# entrenador.net
KiCad netlist of a schematic drawn in EAGLE
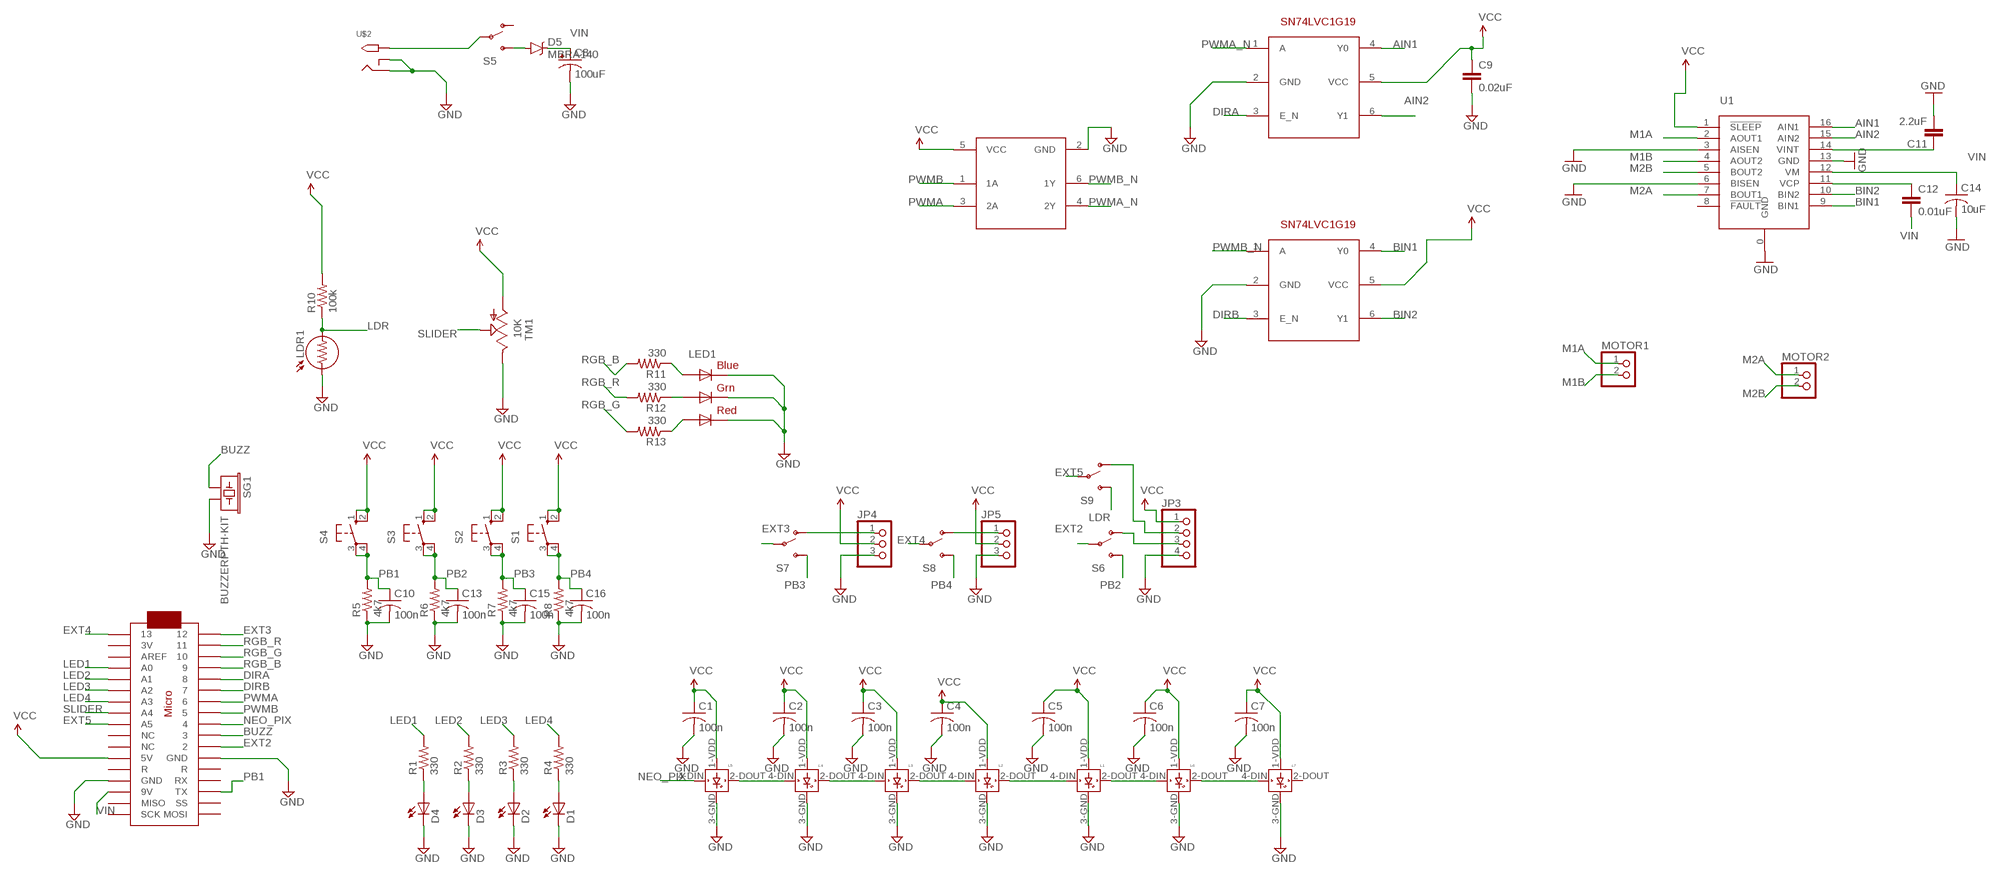
[diagram p0: schematic, sheet 1]

(export (version "E")
  (design (tool "Eeschema 10.0.6"))
  (components
    (comp (ref "C1")
      (value "100n")
      (footprint "eagle-import:C0805")
      (libsource (lib "eagle-import") (part "C-USC0805"))
    )
    (comp (ref "C2")
      (value "100n")
      (footprint "eagle-import:C0805")
      (libsource (lib "eagle-import") (part "C-USC0805"))
    )
    (comp (ref "C3")
      (value "100n")
      (footprint "eagle-import:C0805")
      (libsource (lib "eagle-import") (part "C-USC0805"))
    )
    (comp (ref "C4")
      (value "100n")
      (footprint "eagle-import:C0805")
      (libsource (lib "eagle-import") (part "C-USC0805"))
    )
    (comp (ref "C5")
      (value "100n")
      (footprint "eagle-import:C0805")
      (libsource (lib "eagle-import") (part "C-USC0805"))
    )
    (comp (ref "C6")
      (value "100n")
      (footprint "eagle-import:C0805")
      (libsource (lib "eagle-import") (part "C-USC0805"))
    )
    (comp (ref "C7")
      (value "100n")
      (footprint "eagle-import:C0805")
      (libsource (lib "eagle-import") (part "C-USC0805"))
    )
    (comp (ref "C8")
      (value "100uF")
      (footprint "eagle-import:175TMP-0808")
      (libsource (lib "eagle-import") (part "CPOL-US175TMP-0808"))
    )
    (comp (ref "C9")
      (value "0.02uF")
      (footprint "eagle-import:C0805")
      (libsource (lib "eagle-import") (part "C-EUC0805"))
    )
    (comp (ref "C10")
      (value "100n")
      (footprint "eagle-import:C0805")
      (libsource (lib "eagle-import") (part "C-USC0805"))
    )
    (comp (ref "C11")
      (value "2.2uF")
      (footprint "eagle-import:C0805")
      (libsource (lib "eagle-import") (part "C-EUC0805"))
    )
    (comp (ref "C12")
      (value "0.01uF")
      (footprint "eagle-import:C0805")
      (libsource (lib "eagle-import") (part "C-EUC0805"))
    )
    (comp (ref "C13")
      (value "100n")
      (footprint "eagle-import:C0805")
      (libsource (lib "eagle-import") (part "C-USC0805"))
    )
    (comp (ref "C14")
      (value "10uF")
      (footprint "eagle-import:C0805K")
      (libsource (lib "eagle-import") (part "C-USC0805K"))
    )
    (comp (ref "C15")
      (value "100n")
      (footprint "eagle-import:C0805")
      (libsource (lib "eagle-import") (part "C-USC0805"))
    )
    (comp (ref "C16")
      (value "100n")
      (footprint "eagle-import:C0805")
      (libsource (lib "eagle-import") (part "C-USC0805"))
    )
    (comp (ref "D1")
      (value "LED5MM")
      (footprint "eagle-import:LED5MM")
      (libsource (lib "eagle-import") (part "LED5MM"))
    )
    (comp (ref "D2")
      (value "LED5MM")
      (footprint "eagle-import:LED5MM")
      (libsource (lib "eagle-import") (part "LED5MM"))
    )
    (comp (ref "D3")
      (value "LED5MM")
      (footprint "eagle-import:LED5MM")
      (libsource (lib "eagle-import") (part "LED5MM"))
    )
    (comp (ref "D4")
      (value "LED5MM")
      (footprint "eagle-import:LED5MM")
      (libsource (lib "eagle-import") (part "LED5MM"))
    )
    (comp (ref "D5")
      (value "MBRA140")
      (footprint "eagle-import:SMA-DIODE")
      (libsource (lib "eagle-import") (part "MBRA140"))
    )
    (comp (ref "JP3")
      (value "PINHD-1X4/90")
      (footprint "eagle-import:1X04_90")
      (libsource (lib "eagle-import") (part "PINHD-1X4/90"))
    )
    (comp (ref "JP4")
      (value "PINHD-1X3/90")
      (footprint "eagle-import:1X03_90")
      (libsource (lib "eagle-import") (part "PINHD-1X3/90"))
    )
    (comp (ref "JP5")
      (value "PINHD-1X3/90")
      (footprint "eagle-import:1X03_90")
      (libsource (lib "eagle-import") (part "PINHD-1X3/90"))
    )
    (comp (ref "L1")
      (value "WS2812B")
      (footprint "eagle-import:WS2812B")
      (libsource (lib "eagle-import") (part "WS2812B"))
    )
    (comp (ref "L2")
      (value "WS2812B")
      (footprint "eagle-import:WS2812B")
      (libsource (lib "eagle-import") (part "WS2812B"))
    )
    (comp (ref "L3")
      (value "WS2812B")
      (footprint "eagle-import:WS2812B")
      (libsource (lib "eagle-import") (part "WS2812B"))
    )
    (comp (ref "L4")
      (value "WS2812B")
      (footprint "eagle-import:WS2812B")
      (libsource (lib "eagle-import") (part "WS2812B"))
    )
    (comp (ref "L5")
      (value "WS2812B")
      (footprint "eagle-import:WS2812B")
      (libsource (lib "eagle-import") (part "WS2812B"))
    )
    (comp (ref "L6")
      (value "WS2812B")
      (footprint "eagle-import:WS2812B")
      (libsource (lib "eagle-import") (part "WS2812B"))
    )
    (comp (ref "L7")
      (value "WS2812B")
      (footprint "eagle-import:WS2812B")
      (libsource (lib "eagle-import") (part "WS2812B"))
    )
    (comp (ref "LDR1")
      (value "LDR5MM")
      (footprint "eagle-import:LDR338-54C")
      (libsource (lib "eagle-import") (part "LDR5MM"))
    )
    (comp (ref "LED1")
      (value "RGBLED5050")
      (footprint "eagle-import:RGBLED5050")
      (libsource (lib "eagle-import") (part "RGBLED5050"))
    )
    (comp (ref "MOTOR1")
      (value "PINHD-1X2/90")
      (footprint "eagle-import:1X02_90")
      (libsource (lib "eagle-import") (part "PINHD-1X2/90"))
    )
    (comp (ref "MOTOR2")
      (value "PINHD-1X2/90")
      (footprint "eagle-import:1X02_90")
      (libsource (lib "eagle-import") (part "PINHD-1X2/90"))
    )
    (comp (ref "R1")
      (value "330")
      (footprint "eagle-import:M0805")
      (libsource (lib "eagle-import") (part "R-US_M0805"))
    )
    (comp (ref "R2")
      (value "330")
      (footprint "eagle-import:M0805")
      (libsource (lib "eagle-import") (part "R-US_M0805"))
    )
    (comp (ref "R3")
      (value "330")
      (footprint "eagle-import:M0805")
      (libsource (lib "eagle-import") (part "R-US_M0805"))
    )
    (comp (ref "R4")
      (value "330")
      (footprint "eagle-import:M0805")
      (libsource (lib "eagle-import") (part "R-US_M0805"))
    )
    (comp (ref "R5")
      (value "4k7")
      (footprint "eagle-import:M0805")
      (libsource (lib "eagle-import") (part "R-US_M0805"))
    )
    (comp (ref "R6")
      (value "4k7")
      (footprint "eagle-import:M0805")
      (libsource (lib "eagle-import") (part "R-US_M0805"))
    )
    (comp (ref "R7")
      (value "4k7")
      (footprint "eagle-import:M0805")
      (libsource (lib "eagle-import") (part "R-US_M0805"))
    )
    (comp (ref "R8")
      (value "4k7")
      (footprint "eagle-import:M0805")
      (libsource (lib "eagle-import") (part "R-US_M0805"))
    )
    (comp (ref "R10")
      (value "100k")
      (footprint "eagle-import:M0805")
      (libsource (lib "eagle-import") (part "R-US_M0805"))
    )
    (comp (ref "R11")
      (value "330")
      (footprint "eagle-import:M0805")
      (libsource (lib "eagle-import") (part "R-US_M0805"))
    )
    (comp (ref "R12")
      (value "330")
      (footprint "eagle-import:M0805")
      (libsource (lib "eagle-import") (part "R-US_M0805"))
    )
    (comp (ref "R13")
      (value "330")
      (footprint "eagle-import:M0805")
      (libsource (lib "eagle-import") (part "R-US_M0805"))
    )
    (comp (ref "S1")
      (value "40-XX-ROUND")
      (footprint "eagle-import:B3F-40XX-ROUND")
      (libsource (lib "eagle-import") (part "40-XX-ROUND"))
    )
    (comp (ref "S2")
      (value "40-XX-ROUND")
      (footprint "eagle-import:B3F-40XX-ROUND")
      (libsource (lib "eagle-import") (part "40-XX-ROUND"))
    )
    (comp (ref "S3")
      (value "40-XX-ROUND")
      (footprint "eagle-import:B3F-40XX-ROUND")
      (libsource (lib "eagle-import") (part "40-XX-ROUND"))
    )
    (comp (ref "S4")
      (value "40-XX-ROUND")
      (footprint "eagle-import:B3F-40XX-ROUND")
      (libsource (lib "eagle-import") (part "40-XX-ROUND"))
    )
    (comp (ref "S5")
      (value "SWITCH-SPDT-SMD-A")
      (footprint "eagle-import:SWITCH-SPST-SMD-A")
      (libsource (lib "eagle-import") (part "SWITCH-SPDT-SMD-A"))
    )
    (comp (ref "S6")
      (value "SWITCH-SPDTSS-12F44")
      (footprint "eagle-import:SS-12F44G4")
      (libsource (lib "eagle-import") (part "SWITCH-SPDTSS-12F44"))
    )
    (comp (ref "S7")
      (value "SWITCH-SPDTSS-12F44")
      (footprint "eagle-import:SS-12F44G4")
      (libsource (lib "eagle-import") (part "SWITCH-SPDTSS-12F44"))
    )
    (comp (ref "S8")
      (value "SWITCH-SPDTSS-12F44")
      (footprint "eagle-import:SS-12F44G4")
      (libsource (lib "eagle-import") (part "SWITCH-SPDTSS-12F44"))
    )
    (comp (ref "S9")
      (value "SWITCH-SPDTSS-12F44")
      (footprint "eagle-import:SS-12F44G4")
      (libsource (lib "eagle-import") (part "SWITCH-SPDTSS-12F44"))
    )
    (comp (ref "SG1")
      (value "BUZZERPTH-KIT")
      (footprint "eagle-import:BUZZER-12MM-KIT")
      (libsource (lib "eagle-import") (part "BUZZERPTH-KIT"))
    )
    (comp (ref "TM1")
      (value "10K")
      (footprint "eagle-import:SLIDEPOT-60")
      (libsource (lib "eagle-import") (part "TRIMSLIDEPOT-60"))
    )
    (comp (ref "U$1")
      (value "SN74LVC1G19SN74LVC1G19-DBVR")
      (footprint "eagle-import:SOT23-6")
      (libsource (lib "eagle-import") (part "SN74LVC1G19SN74LVC1G19-DBVR"))
    )
    (comp (ref "U$2")
      (value "2.1MMJACKTHM")
      (footprint "eagle-import:PJ-102A")
      (libsource (lib "eagle-import") (part "2.1MMJACKTHM"))
    )
    (comp (ref "U$8")
      (value "ARDUINOMICRO")
      (footprint "eagle-import:ARDUINOMICRO")
      (libsource (lib "eagle-import") (part "ARDUINOMICRO"))
    )
    (comp (ref "U$9")
      (value "SN74LVC1G19SN74LVC1G19-DBVR")
      (footprint "eagle-import:SOT23-6")
      (libsource (lib "eagle-import") (part "SN74LVC1G19SN74LVC1G19-DBVR"))
    )
    (comp (ref "U$10")
      (value "SN74LVC2G04SOT23-6")
      (footprint "eagle-import:SOT23-6")
      (libsource (lib "eagle-import") (part "SN74LVC2G04SOT23-6"))
    )
    (comp (ref "U1")
      (value "DRV8833")
      (footprint "eagle-import:PWP16")
      (libsource (lib "eagle-import") (part "DRV8833"))
    )
  )
  (nets
    (net (code "1") (name "/AIN1") (class "Default")
      (node (ref "U$1") (pin "4") (pinfunction "Y0_4") (pintype "bidirectional"))
      (node (ref "U1") (pin "16") (pinfunction "AIN1_16") (pintype "bidirectional"))
    )
    (net (code "2") (name "/AIN2") (class "Default")
      (node (ref "U$1") (pin "6") (pinfunction "Y1_6") (pintype "bidirectional"))
      (node (ref "U1") (pin "15") (pinfunction "AIN2_15") (pintype "bidirectional"))
    )
    (net (code "3") (name "/BIN1") (class "Default")
      (node (ref "U$9") (pin "4") (pinfunction "Y0_4") (pintype "bidirectional"))
      (node (ref "U1") (pin "9") (pinfunction "BIN1_9") (pintype "bidirectional"))
    )
    (net (code "4") (name "/BIN2") (class "Default")
      (node (ref "U$9") (pin "6") (pinfunction "Y1_6") (pintype "bidirectional"))
      (node (ref "U1") (pin "10") (pinfunction "BIN2_10") (pintype "bidirectional"))
    )
    (net (code "5") (name "/BUZZ") (class "Default")
      (node (ref "SG1") (pin "+") (pinfunction "1_+") (pintype "passive"))
      (node (ref "U$8") (pin "P$10") (pinfunction "3_P$10") (pintype "bidirectional"))
    )
    (net (code "6") (name "/DIRA") (class "Default")
      (node (ref "U$1") (pin "3") (pinfunction "E_N_3") (pintype "bidirectional"))
      (node (ref "U$8") (pin "P$5") (pinfunction "8_P$5") (pintype "bidirectional"))
    )
    (net (code "7") (name "/DIRB") (class "Default")
      (node (ref "U$8") (pin "P$6") (pinfunction "7_P$6") (pintype "bidirectional"))
      (node (ref "U$9") (pin "3") (pinfunction "E_N_3") (pintype "bidirectional"))
    )
    (net (code "8") (name "/EXT2") (class "Default")
      (node (ref "S6") (pin "2") (pinfunction "P_2") (pintype "passive"))
      (node (ref "U$8") (pin "P$11") (pinfunction "2_P$11") (pintype "bidirectional"))
    )
    (net (code "9") (name "/EXT3") (class "Default")
      (node (ref "S7") (pin "2") (pinfunction "P_2") (pintype "passive"))
      (node (ref "U$8") (pin "P$1") (pinfunction "12_P$1") (pintype "bidirectional"))
    )
    (net (code "10") (name "/EXT4") (class "Default")
      (node (ref "S8") (pin "2") (pinfunction "P_2") (pintype "passive"))
      (node (ref "U$8") (pin "P$34") (pinfunction "13_P$34") (pintype "bidirectional"))
    )
    (net (code "11") (name "/EXT5") (class "Default")
      (node (ref "S9") (pin "2") (pinfunction "P_2") (pintype "passive"))
      (node (ref "U$8") (pin "P$26") (pinfunction "A5_P$26") (pintype "bidirectional"))
    )
    (net (code "12") (name "/LDR") (class "Default")
      (node (ref "LDR1") (pin "2") (pinfunction "2_2") (pintype "passive"))
      (node (ref "R10") (pin "1") (pinfunction "1_1") (pintype "passive"))
      (node (ref "S9") (pin "3") (pinfunction "S_3") (pintype "passive"))
    )
    (net (code "13") (name "/LED1") (class "Default")
      (node (ref "R1") (pin "2") (pinfunction "2_2") (pintype "passive"))
      (node (ref "U$8") (pin "P$31") (pinfunction "A0_P$31") (pintype "bidirectional"))
    )
    (net (code "14") (name "/LED2") (class "Default")
      (node (ref "R2") (pin "2") (pinfunction "2_2") (pintype "passive"))
      (node (ref "U$8") (pin "P$30") (pinfunction "A1_P$30") (pintype "bidirectional"))
    )
    (net (code "15") (name "/LED3") (class "Default")
      (node (ref "R3") (pin "2") (pinfunction "2_2") (pintype "passive"))
      (node (ref "U$8") (pin "P$29") (pinfunction "A2_P$29") (pintype "bidirectional"))
    )
    (net (code "16") (name "/LED4") (class "Default")
      (node (ref "R4") (pin "2") (pinfunction "2_2") (pintype "passive"))
      (node (ref "U$8") (pin "P$28") (pinfunction "A3_P$28") (pintype "bidirectional"))
    )
    (net (code "17") (name "/M1A") (class "Default")
      (node (ref "MOTOR1") (pin "1") (pinfunction "1_1") (pintype "passive"))
      (node (ref "U1") (pin "2") (pinfunction "AOUT1_2") (pintype "bidirectional"))
    )
    (net (code "18") (name "/M1B") (class "Default")
      (node (ref "MOTOR1") (pin "2") (pinfunction "2_2") (pintype "passive"))
      (node (ref "U1") (pin "4") (pinfunction "AOUT2_4") (pintype "bidirectional"))
    )
    (net (code "19") (name "/M2A") (class "Default")
      (node (ref "MOTOR2") (pin "1") (pinfunction "1_1") (pintype "passive"))
      (node (ref "U1") (pin "7") (pinfunction "BOUT1_7") (pintype "bidirectional"))
    )
    (net (code "20") (name "/M2B") (class "Default")
      (node (ref "MOTOR2") (pin "2") (pinfunction "2_2") (pintype "passive"))
      (node (ref "U1") (pin "5") (pinfunction "BOUT2_5") (pintype "bidirectional"))
    )
    (net (code "21") (name "/NEO_PIX") (class "Default")
      (node (ref "L5") (pin "4-DIN") (pinfunction "DIN_4-DIN") (pintype "input"))
      (node (ref "U$8") (pin "P$9") (pinfunction "4_P$9") (pintype "bidirectional"))
    )
    (net (code "22") (name "/PB1") (class "Default")
      (node (ref "C10") (pin "1") (pinfunction "1_1") (pintype "passive"))
      (node (ref "R5") (pin "2") (pinfunction "2_2") (pintype "passive"))
      (node (ref "S4") (pin "3") (pinfunction "P_3") (pintype "passive"))
      (node (ref "S4") (pin "4") (pinfunction "P1_4") (pintype "passive"))
      (node (ref "U$8") (pin "P$15") (pinfunction "TX_P$15") (pintype "bidirectional"))
    )
    (net (code "23") (name "/PB2") (class "Default")
      (node (ref "C13") (pin "1") (pinfunction "1_1") (pintype "passive"))
      (node (ref "R6") (pin "2") (pinfunction "2_2") (pintype "passive"))
      (node (ref "S3") (pin "3") (pinfunction "P_3") (pintype "passive"))
      (node (ref "S3") (pin "4") (pinfunction "P1_4") (pintype "passive"))
      (node (ref "S6") (pin "3") (pinfunction "S_3") (pintype "passive"))
    )
    (net (code "24") (name "/PB3") (class "Default")
      (node (ref "C15") (pin "1") (pinfunction "1_1") (pintype "passive"))
      (node (ref "R7") (pin "2") (pinfunction "2_2") (pintype "passive"))
      (node (ref "S2") (pin "3") (pinfunction "P_3") (pintype "passive"))
      (node (ref "S2") (pin "4") (pinfunction "P1_4") (pintype "passive"))
      (node (ref "S7") (pin "3") (pinfunction "S_3") (pintype "passive"))
    )
    (net (code "25") (name "/PB4") (class "Default")
      (node (ref "C16") (pin "1") (pinfunction "1_1") (pintype "passive"))
      (node (ref "R8") (pin "2") (pinfunction "2_2") (pintype "passive"))
      (node (ref "S1") (pin "3") (pinfunction "P_3") (pintype "passive"))
      (node (ref "S1") (pin "4") (pinfunction "P1_4") (pintype "passive"))
      (node (ref "S8") (pin "3") (pinfunction "S_3") (pintype "passive"))
    )
    (net (code "26") (name "/PWMA") (class "Default")
      (node (ref "U$10") (pin "3") (pinfunction "2A_3") (pintype "bidirectional"))
      (node (ref "U$8") (pin "P$7") (pinfunction "6_P$7") (pintype "bidirectional"))
    )
    (net (code "27") (name "/PWMA_N") (class "Default")
      (node (ref "U$1") (pin "1") (pinfunction "A_1") (pintype "bidirectional"))
      (node (ref "U$10") (pin "4") (pinfunction "2Y_4") (pintype "bidirectional"))
    )
    (net (code "28") (name "/PWMB") (class "Default")
      (node (ref "U$10") (pin "1") (pinfunction "1A_1") (pintype "bidirectional"))
      (node (ref "U$8") (pin "P$8") (pinfunction "5_P$8") (pintype "bidirectional"))
    )
    (net (code "29") (name "/PWMB_N") (class "Default")
      (node (ref "U$10") (pin "6") (pinfunction "1Y_6") (pintype "bidirectional"))
      (node (ref "U$9") (pin "1") (pinfunction "A_1") (pintype "bidirectional"))
    )
    (net (code "30") (name "/RGB_B") (class "Default")
      (node (ref "R11") (pin "2") (pinfunction "2_2") (pintype "passive"))
      (node (ref "U$8") (pin "P$4") (pinfunction "9_P$4") (pintype "bidirectional"))
    )
    (net (code "31") (name "/RGB_G") (class "Default")
      (node (ref "R13") (pin "2") (pinfunction "2_2") (pintype "passive"))
      (node (ref "U$8") (pin "P$3") (pinfunction "10_P$3") (pintype "bidirectional"))
    )
    (net (code "32") (name "/RGB_R") (class "Default")
      (node (ref "R12") (pin "2") (pinfunction "2_2") (pintype "passive"))
      (node (ref "U$8") (pin "P$2") (pinfunction "11_P$2") (pintype "bidirectional"))
    )
    (net (code "33") (name "/SLIDER") (class "Default")
      (node (ref "TM1") (pin "B") (pinfunction "S_B") (pintype "passive"))
      (node (ref "U$8") (pin "P$27") (pinfunction "A4_P$27") (pintype "bidirectional"))
    )
    (net (code "34") (name "/VIN") (class "Default")
      (node (ref "C12") (pin "2") (pinfunction "2_2") (pintype "passive"))
      (node (ref "C14") (pin "1") (pinfunction "1_1") (pintype "passive"))
      (node (ref "C8") (pin "+") (pinfunction "+_+") (pintype "passive"))
      (node (ref "D5") (pin "C") (pinfunction "C_C") (pintype "passive"))
      (node (ref "U$8") (pin "P$20") (pinfunction "9V_P$20") (pintype "bidirectional"))
      (node (ref "U1") (pin "12") (pinfunction "VM_12") (pintype "bidirectional"))
    )
    (net (code "35") (name "GND") (class "Default")
      (node (ref "C1") (pin "2") (pinfunction "2_2") (pintype "passive"))
      (node (ref "C10") (pin "2") (pinfunction "2_2") (pintype "passive"))
      (node (ref "C11") (pin "2") (pinfunction "2_2") (pintype "passive"))
      (node (ref "C13") (pin "2") (pinfunction "2_2") (pintype "passive"))
      (node (ref "C14") (pin "2") (pinfunction "2_2") (pintype "passive"))
      (node (ref "C15") (pin "2") (pinfunction "2_2") (pintype "passive"))
      (node (ref "C16") (pin "2") (pinfunction "2_2") (pintype "passive"))
      (node (ref "C2") (pin "2") (pinfunction "2_2") (pintype "passive"))
      (node (ref "C3") (pin "2") (pinfunction "2_2") (pintype "passive"))
      (node (ref "C4") (pin "2") (pinfunction "2_2") (pintype "passive"))
      (node (ref "C5") (pin "2") (pinfunction "2_2") (pintype "passive"))
      (node (ref "C6") (pin "2") (pinfunction "2_2") (pintype "passive"))
      (node (ref "C7") (pin "2") (pinfunction "2_2") (pintype "passive"))
      (node (ref "C8") (pin "-") (pinfunction "-_-") (pintype "passive"))
      (node (ref "C9") (pin "2") (pinfunction "2_2") (pintype "passive"))
      (node (ref "D1") (pin "K") (pinfunction "C_K") (pintype "passive"))
      (node (ref "D2") (pin "K") (pinfunction "C_K") (pintype "passive"))
      (node (ref "D3") (pin "K") (pinfunction "C_K") (pintype "passive"))
      (node (ref "D4") (pin "K") (pinfunction "C_K") (pintype "passive"))
      (node (ref "JP3") (pin "4") (pinfunction "4_4") (pintype "passive"))
      (node (ref "JP4") (pin "3") (pinfunction "3_3") (pintype "passive"))
      (node (ref "JP5") (pin "3") (pinfunction "3_3") (pintype "passive"))
      (node (ref "L1") (pin "3-GND") (pinfunction "GND_3-GND") (pintype "bidirectional"))
      (node (ref "L2") (pin "3-GND") (pinfunction "GND_3-GND") (pintype "bidirectional"))
      (node (ref "L3") (pin "3-GND") (pinfunction "GND_3-GND") (pintype "bidirectional"))
      (node (ref "L4") (pin "3-GND") (pinfunction "GND_3-GND") (pintype "bidirectional"))
      (node (ref "L5") (pin "3-GND") (pinfunction "GND_3-GND") (pintype "bidirectional"))
      (node (ref "L6") (pin "3-GND") (pinfunction "GND_3-GND") (pintype "bidirectional"))
      (node (ref "L7") (pin "3-GND") (pinfunction "GND_3-GND") (pintype "bidirectional"))
      (node (ref "LDR1") (pin "1") (pinfunction "1_1") (pintype "passive"))
      (node (ref "LED1") (pin "4") (pinfunction "BLUE_C_4") (pintype "bidirectional"))
      (node (ref "LED1") (pin "5") (pinfunction "RED_C_5") (pintype "bidirectional"))
      (node (ref "LED1") (pin "6") (pinfunction "GREEN_C_6") (pintype "bidirectional"))
      (node (ref "R5") (pin "1") (pinfunction "1_1") (pintype "passive"))
      (node (ref "R6") (pin "1") (pinfunction "1_1") (pintype "passive"))
      (node (ref "R7") (pin "1") (pinfunction "1_1") (pintype "passive"))
      (node (ref "R8") (pin "1") (pinfunction "1_1") (pintype "passive"))
      (node (ref "SG1") (pin "-") (pinfunction "2_-") (pintype "passive"))
      (node (ref "TM1") (pin "C") (pinfunction "E_C") (pintype "passive"))
      (node (ref "U$1") (pin "2") (pinfunction "GND_2") (pintype "bidirectional"))
      (node (ref "U$10") (pin "2") (pinfunction "GND_2") (pintype "bidirectional"))
      (node (ref "U$2") (pin "RING") (pinfunction "RING_RING") (pintype "bidirectional"))
      (node (ref "U$2") (pin "RING_SW") (pinfunction "RING_SW_RING_SW") (pintype "bidirectional"))
      (node (ref "U$8") (pin "P$12") (pinfunction "GND_P$12") (pintype "bidirectional"))
      (node (ref "U$8") (pin "P$21") (pinfunction "GND_P$21") (pintype "bidirectional"))
      (node (ref "U$9") (pin "2") (pinfunction "GND_2") (pintype "bidirectional"))
      (node (ref "U1") (pin "0") (pinfunction "GND_0") (pintype "bidirectional"))
      (node (ref "U1") (pin "13") (pinfunction "GND_13") (pintype "bidirectional"))
      (node (ref "U1") (pin "3") (pinfunction "AISEN_3") (pintype "bidirectional"))
      (node (ref "U1") (pin "6") (pinfunction "BISEN_6") (pintype "bidirectional"))
    )
    (net (code "36") (name "Net-(D1-PadA)") (class "Default")
      (node (ref "D1") (pin "A") (pinfunction "A_A") (pintype "passive"))
      (node (ref "R4") (pin "1") (pinfunction "1_1") (pintype "passive"))
    )
    (net (code "37") (name "Net-(D2-PadA)") (class "Default")
      (node (ref "D2") (pin "A") (pinfunction "A_A") (pintype "passive"))
      (node (ref "R3") (pin "1") (pinfunction "1_1") (pintype "passive"))
    )
    (net (code "38") (name "Net-(D3-PadA)") (class "Default")
      (node (ref "D3") (pin "A") (pinfunction "A_A") (pintype "passive"))
      (node (ref "R2") (pin "1") (pinfunction "1_1") (pintype "passive"))
    )
    (net (code "39") (name "Net-(D4-PadA)") (class "Default")
      (node (ref "D4") (pin "A") (pinfunction "A_A") (pintype "passive"))
      (node (ref "R1") (pin "1") (pinfunction "1_1") (pintype "passive"))
    )
    (net (code "40") (name "Net-(L1-DIN)") (class "Default")
      (node (ref "L1") (pin "4-DIN") (pinfunction "DIN_4-DIN") (pintype "input"))
      (node (ref "L2") (pin "2-DOUT") (pinfunction "DOUT_2-DOUT") (pintype "output"))
    )
    (net (code "41") (name "Net-(L1-DOUT)") (class "Default")
      (node (ref "L1") (pin "2-DOUT") (pinfunction "DOUT_2-DOUT") (pintype "output"))
      (node (ref "L6") (pin "4-DIN") (pinfunction "DIN_4-DIN") (pintype "input"))
    )
    (net (code "42") (name "Net-(L2-DIN)") (class "Default")
      (node (ref "L2") (pin "4-DIN") (pinfunction "DIN_4-DIN") (pintype "input"))
      (node (ref "L3") (pin "2-DOUT") (pinfunction "DOUT_2-DOUT") (pintype "output"))
    )
    (net (code "43") (name "Net-(L3-DIN)") (class "Default")
      (node (ref "L3") (pin "4-DIN") (pinfunction "DIN_4-DIN") (pintype "input"))
      (node (ref "L4") (pin "2-DOUT") (pinfunction "DOUT_2-DOUT") (pintype "output"))
    )
    (net (code "44") (name "Net-(L4-DIN)") (class "Default")
      (node (ref "L4") (pin "4-DIN") (pinfunction "DIN_4-DIN") (pintype "input"))
      (node (ref "L5") (pin "2-DOUT") (pinfunction "DOUT_2-DOUT") (pintype "output"))
    )
    (net (code "45") (name "Net-(L6-DOUT)") (class "Default")
      (node (ref "L6") (pin "2-DOUT") (pinfunction "DOUT_2-DOUT") (pintype "output"))
      (node (ref "L7") (pin "4-DIN") (pinfunction "DIN_4-DIN") (pintype "input"))
    )
    (net (code "46") (name "Net-(LED1-BLUE_A)") (class "Default")
      (node (ref "LED1") (pin "3") (pinfunction "BLUE_A_3") (pintype "bidirectional"))
      (node (ref "R11") (pin "1") (pinfunction "1_1") (pintype "passive"))
    )
    (net (code "47") (name "Net-(LED1-GREEN_A)") (class "Default")
      (node (ref "LED1") (pin "1") (pinfunction "GREEN_A_1") (pintype "bidirectional"))
      (node (ref "R12") (pin "1") (pinfunction "1_1") (pintype "passive"))
    )
    (net (code "48") (name "Net-(LED1-RED_A)") (class "Default")
      (node (ref "LED1") (pin "2") (pinfunction "RED_A_2") (pintype "bidirectional"))
      (node (ref "R13") (pin "1") (pinfunction "1_1") (pintype "passive"))
    )
    (net (code "49") (name "Net-(S5-P)") (class "Default")
      (node (ref "S5") (pin "2") (pinfunction "P_2") (pintype "passive"))
      (node (ref "U$2") (pin "TIP") (pinfunction "TIP_TIP") (pintype "bidirectional"))
    )
    (net (code "50") (name "Net-(S5-S)") (class "Default")
      (node (ref "D5") (pin "A") (pinfunction "A_A") (pintype "passive"))
      (node (ref "S5") (pin "3") (pinfunction "S_3") (pintype "passive"))
    )
    (net (code "51") (name "Net-(S6-O)") (class "Default")
      (node (ref "JP3") (pin "3") (pinfunction "3_3") (pintype "passive"))
      (node (ref "S6") (pin "1") (pinfunction "O_1") (pintype "passive"))
    )
    (net (code "52") (name "Net-(S7-O)") (class "Default")
      (node (ref "JP4") (pin "1") (pinfunction "1_1") (pintype "passive"))
      (node (ref "S7") (pin "1") (pinfunction "O_1") (pintype "passive"))
    )
    (net (code "53") (name "Net-(S8-O)") (class "Default")
      (node (ref "JP5") (pin "1") (pinfunction "1_1") (pintype "passive"))
      (node (ref "S8") (pin "1") (pinfunction "O_1") (pintype "passive"))
    )
    (net (code "54") (name "Net-(S9-O)") (class "Default")
      (node (ref "JP3") (pin "2") (pinfunction "2_2") (pintype "passive"))
      (node (ref "S9") (pin "1") (pinfunction "O_1") (pintype "passive"))
    )
    (net (code "55") (name "Net-(U1-VCP)") (class "Default")
      (node (ref "C12") (pin "1") (pinfunction "1_1") (pintype "passive"))
      (node (ref "U1") (pin "11") (pinfunction "VCP_11") (pintype "bidirectional"))
    )
    (net (code "56") (name "Net-(U1-VINT)") (class "Default")
      (node (ref "C11") (pin "1") (pinfunction "1_1") (pintype "passive"))
      (node (ref "U1") (pin "14") (pinfunction "VINT_14") (pintype "bidirectional"))
    )
    (net (code "57") (name "VCC") (class "Default")
      (node (ref "C1") (pin "1") (pinfunction "1_1") (pintype "passive"))
      (node (ref "C2") (pin "1") (pinfunction "1_1") (pintype "passive"))
      (node (ref "C3") (pin "1") (pinfunction "1_1") (pintype "passive"))
      (node (ref "C4") (pin "1") (pinfunction "1_1") (pintype "passive"))
      (node (ref "C5") (pin "1") (pinfunction "1_1") (pintype "passive"))
      (node (ref "C6") (pin "1") (pinfunction "1_1") (pintype "passive"))
      (node (ref "C7") (pin "1") (pinfunction "1_1") (pintype "passive"))
      (node (ref "C9") (pin "1") (pinfunction "1_1") (pintype "passive"))
      (node (ref "JP3") (pin "1") (pinfunction "1_1") (pintype "passive"))
      (node (ref "JP4") (pin "2") (pinfunction "2_2") (pintype "passive"))
      (node (ref "JP5") (pin "2") (pinfunction "2_2") (pintype "passive"))
      (node (ref "L1") (pin "1-VDD") (pinfunction "VDD_1-VDD") (pintype "bidirectional"))
      (node (ref "L2") (pin "1-VDD") (pinfunction "VDD_1-VDD") (pintype "bidirectional"))
      (node (ref "L3") (pin "1-VDD") (pinfunction "VDD_1-VDD") (pintype "bidirectional"))
      (node (ref "L4") (pin "1-VDD") (pinfunction "VDD_1-VDD") (pintype "bidirectional"))
      (node (ref "L5") (pin "1-VDD") (pinfunction "VDD_1-VDD") (pintype "bidirectional"))
      (node (ref "L6") (pin "1-VDD") (pinfunction "VDD_1-VDD") (pintype "bidirectional"))
      (node (ref "L7") (pin "1-VDD") (pinfunction "VDD_1-VDD") (pintype "bidirectional"))
      (node (ref "R10") (pin "2") (pinfunction "2_2") (pintype "passive"))
      (node (ref "S1") (pin "1") (pinfunction "S_1") (pintype "passive"))
      (node (ref "S1") (pin "2") (pinfunction "S1_2") (pintype "passive"))
      (node (ref "S2") (pin "1") (pinfunction "S_1") (pintype "passive"))
      (node (ref "S2") (pin "2") (pinfunction "S1_2") (pintype "passive"))
      (node (ref "S3") (pin "1") (pinfunction "S_1") (pintype "passive"))
      (node (ref "S3") (pin "2") (pinfunction "S1_2") (pintype "passive"))
      (node (ref "S4") (pin "1") (pinfunction "S_1") (pintype "passive"))
      (node (ref "S4") (pin "2") (pinfunction "S1_2") (pintype "passive"))
      (node (ref "TM1") (pin "A") (pinfunction "A_A") (pintype "passive"))
      (node (ref "U$1") (pin "5") (pinfunction "VCC_5") (pintype "bidirectional"))
      (node (ref "U$10") (pin "5") (pinfunction "VCC_5") (pintype "bidirectional"))
      (node (ref "U$8") (pin "P$23") (pinfunction "5V_P$23") (pintype "bidirectional"))
      (node (ref "U$9") (pin "5") (pinfunction "VCC_5") (pintype "bidirectional"))
      (node (ref "U1") (pin "1") (pinfunction "~{SLEEP}_1") (pintype "bidirectional"))
    )
    (net (code "58") (name "unconnected-(L7-DOUT-Pad2-DOUT)") (class "Default")
      (node (ref "L7") (pin "2-DOUT") (pinfunction "DOUT_2-DOUT") (pintype "output"))
    )
    (net (code "59") (name "unconnected-(S5-O-Pad1)") (class "Default")
      (node (ref "S5") (pin "1") (pinfunction "O_1") (pintype "passive"))
    )
    (net (code "60") (name "unconnected-(U$8-3V-PadP$33)") (class "Default")
      (node (ref "U$8") (pin "P$33") (pinfunction "3V_P$33") (pintype "bidirectional"))
    )
    (net (code "61") (name "unconnected-(U$8-AREF-PadP$32)") (class "Default")
      (node (ref "U$8") (pin "P$32") (pinfunction "AREF_P$32") (pintype "bidirectional"))
    )
    (net (code "62") (name "unconnected-(U$8-MISO-PadP$19)") (class "Default")
      (node (ref "U$8") (pin "P$19") (pinfunction "MISO_P$19") (pintype "bidirectional"))
    )
    (net (code "63") (name "unconnected-(U$8-MOSI-PadP$17)") (class "Default")
      (node (ref "U$8") (pin "P$17") (pinfunction "MOSI_P$17") (pintype "bidirectional"))
    )
    (net (code "64") (name "unconnected-(U$8-NC-PadP$24)") (class "Default")
      (node (ref "U$8") (pin "P$24") (pinfunction "NC_P$24") (pintype "bidirectional"))
    )
    (net (code "65") (name "unconnected-(U$8-NC-PadP$25)") (class "Default")
      (node (ref "U$8") (pin "P$25") (pinfunction "NC_P$25") (pintype "bidirectional"))
    )
    (net (code "66") (name "unconnected-(U$8-R-PadP$13)") (class "Default")
      (node (ref "U$8") (pin "P$13") (pinfunction "R_P$13") (pintype "bidirectional"))
    )
    (net (code "67") (name "unconnected-(U$8-R-PadP$22)") (class "Default")
      (node (ref "U$8") (pin "P$22") (pinfunction "R_P$22") (pintype "bidirectional"))
    )
    (net (code "68") (name "unconnected-(U$8-RX-PadP$14)") (class "Default")
      (node (ref "U$8") (pin "P$14") (pinfunction "RX_P$14") (pintype "bidirectional"))
    )
    (net (code "69") (name "unconnected-(U$8-SCK-PadP$18)") (class "Default")
      (node (ref "U$8") (pin "P$18") (pinfunction "SCK_P$18") (pintype "bidirectional"))
    )
    (net (code "70") (name "unconnected-(U$8-SS-PadP$16)") (class "Default")
      (node (ref "U$8") (pin "P$16") (pinfunction "SS_P$16") (pintype "bidirectional"))
    )
    (net (code "71") (name "unconnected-(U1-~{FAULT}-Pad8)") (class "Default")
      (node (ref "U1") (pin "8") (pinfunction "~{FAULT}_8") (pintype "bidirectional"))
    )
  )
)
